# riffle-proto-0_1_8_0.net
KiCad netlist of a schematic drawn in EAGLE
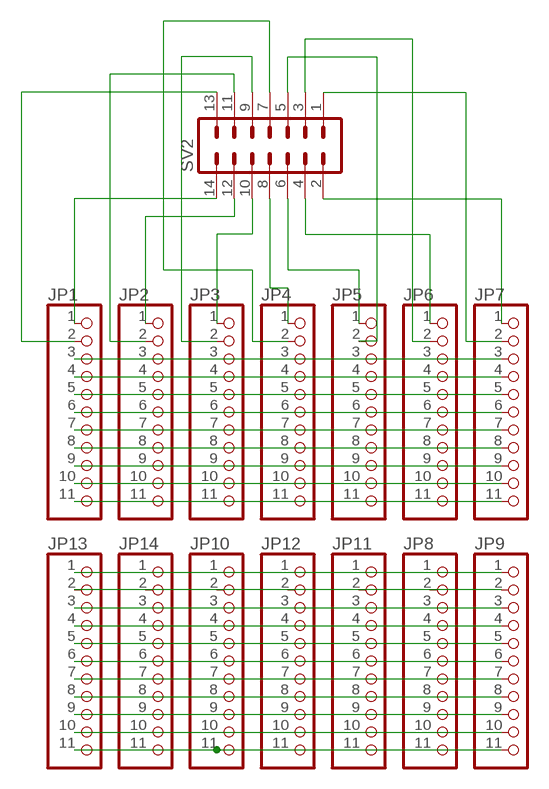
[diagram p0: schematic, sheet 1]

(export (version "E")
  (design (tool "Eeschema 10.0.6"))
  (components
    (comp (ref "JP1")
      (value "HEADER-1X1176MIL")
      (footprint "eagle-import:1X11_ROUND_76")
      (libsource (lib "eagle-import") (part "HEADER-1X1176MIL"))
    )
    (comp (ref "JP2")
      (value "HEADER-1X1176MIL")
      (footprint "eagle-import:1X11_ROUND_76")
      (libsource (lib "eagle-import") (part "HEADER-1X1176MIL"))
    )
    (comp (ref "JP3")
      (value "HEADER-1X1176MIL")
      (footprint "eagle-import:1X11_ROUND_76")
      (libsource (lib "eagle-import") (part "HEADER-1X1176MIL"))
    )
    (comp (ref "JP4")
      (value "HEADER-1X1176MIL")
      (footprint "eagle-import:1X11_ROUND_76")
      (libsource (lib "eagle-import") (part "HEADER-1X1176MIL"))
    )
    (comp (ref "JP5")
      (value "HEADER-1X1176MIL")
      (footprint "eagle-import:1X11_ROUND_76")
      (libsource (lib "eagle-import") (part "HEADER-1X1176MIL"))
    )
    (comp (ref "JP6")
      (value "HEADER-1X1176MIL")
      (footprint "eagle-import:1X11_ROUND_76")
      (libsource (lib "eagle-import") (part "HEADER-1X1176MIL"))
    )
    (comp (ref "JP7")
      (value "HEADER-1X1176MIL")
      (footprint "eagle-import:1X11_ROUND_76")
      (libsource (lib "eagle-import") (part "HEADER-1X1176MIL"))
    )
    (comp (ref "JP8")
      (value "HEADER-1X1176MIL")
      (footprint "eagle-import:1X11_ROUND_76")
      (libsource (lib "eagle-import") (part "HEADER-1X1176MIL"))
    )
    (comp (ref "JP9")
      (value "HEADER-1X1176MIL")
      (footprint "eagle-import:1X11_ROUND_76")
      (libsource (lib "eagle-import") (part "HEADER-1X1176MIL"))
    )
    (comp (ref "JP10")
      (value "HEADER-1X1176MIL")
      (footprint "eagle-import:1X11_ROUND_76")
      (libsource (lib "eagle-import") (part "HEADER-1X1176MIL"))
    )
    (comp (ref "JP11")
      (value "HEADER-1X1176MIL")
      (footprint "eagle-import:1X11_ROUND_76")
      (libsource (lib "eagle-import") (part "HEADER-1X1176MIL"))
    )
    (comp (ref "JP12")
      (value "HEADER-1X1176MIL")
      (footprint "eagle-import:1X11_ROUND_76")
      (libsource (lib "eagle-import") (part "HEADER-1X1176MIL"))
    )
    (comp (ref "JP13")
      (value "HEADER-1X1176MIL")
      (footprint "eagle-import:1X11_ROUND_76")
      (libsource (lib "eagle-import") (part "HEADER-1X1176MIL"))
    )
    (comp (ref "JP14")
      (value "HEADER-1X1176MIL")
      (footprint "eagle-import:1X11_ROUND_76")
      (libsource (lib "eagle-import") (part "HEADER-1X1176MIL"))
    )
    (comp (ref "SV2")
      (value "MA07-2")
      (footprint "eagle-import:MA07-2")
      (libsource (lib "eagle-import") (part "MA07-2"))
    )
  )
  (nets
    (net (code "1") (name "Net-(JP1-Pad1)") (class "Default")
      (node (ref "JP1") (pin "1") (pinfunction "1_1") (pintype "passive"))
      (node (ref "SV2") (pin "14") (pinfunction "14_14") (pintype "passive"))
    )
    (net (code "2") (name "Net-(JP1-Pad2)") (class "Default")
      (node (ref "JP1") (pin "2") (pinfunction "2_2") (pintype "passive"))
      (node (ref "SV2") (pin "13") (pinfunction "13_13") (pintype "passive"))
    )
    (net (code "3") (name "Net-(JP1-Pad3)") (class "Default")
      (node (ref "JP1") (pin "3") (pinfunction "3_3") (pintype "passive"))
      (node (ref "JP2") (pin "3") (pinfunction "3_3") (pintype "passive"))
      (node (ref "JP3") (pin "3") (pinfunction "3_3") (pintype "passive"))
      (node (ref "JP4") (pin "3") (pinfunction "3_3") (pintype "passive"))
      (node (ref "JP5") (pin "3") (pinfunction "3_3") (pintype "passive"))
      (node (ref "JP6") (pin "3") (pinfunction "3_3") (pintype "passive"))
      (node (ref "JP7") (pin "3") (pinfunction "3_3") (pintype "passive"))
    )
    (net (code "4") (name "Net-(JP1-Pad4)") (class "Default")
      (node (ref "JP1") (pin "4") (pinfunction "4_4") (pintype "passive"))
      (node (ref "JP2") (pin "4") (pinfunction "4_4") (pintype "passive"))
      (node (ref "JP3") (pin "4") (pinfunction "4_4") (pintype "passive"))
      (node (ref "JP4") (pin "4") (pinfunction "4_4") (pintype "passive"))
      (node (ref "JP5") (pin "4") (pinfunction "4_4") (pintype "passive"))
      (node (ref "JP6") (pin "4") (pinfunction "4_4") (pintype "passive"))
      (node (ref "JP7") (pin "4") (pinfunction "4_4") (pintype "passive"))
    )
    (net (code "5") (name "Net-(JP1-Pad5)") (class "Default")
      (node (ref "JP1") (pin "5") (pinfunction "5_5") (pintype "passive"))
      (node (ref "JP2") (pin "5") (pinfunction "5_5") (pintype "passive"))
      (node (ref "JP3") (pin "5") (pinfunction "5_5") (pintype "passive"))
      (node (ref "JP4") (pin "5") (pinfunction "5_5") (pintype "passive"))
      (node (ref "JP5") (pin "5") (pinfunction "5_5") (pintype "passive"))
      (node (ref "JP6") (pin "5") (pinfunction "5_5") (pintype "passive"))
      (node (ref "JP7") (pin "5") (pinfunction "5_5") (pintype "passive"))
    )
    (net (code "6") (name "Net-(JP1-Pad6)") (class "Default")
      (node (ref "JP1") (pin "6") (pinfunction "6_6") (pintype "passive"))
      (node (ref "JP2") (pin "6") (pinfunction "6_6") (pintype "passive"))
      (node (ref "JP3") (pin "6") (pinfunction "6_6") (pintype "passive"))
      (node (ref "JP4") (pin "6") (pinfunction "6_6") (pintype "passive"))
      (node (ref "JP5") (pin "6") (pinfunction "6_6") (pintype "passive"))
      (node (ref "JP6") (pin "6") (pinfunction "6_6") (pintype "passive"))
      (node (ref "JP7") (pin "6") (pinfunction "6_6") (pintype "passive"))
    )
    (net (code "7") (name "Net-(JP1-Pad7)") (class "Default")
      (node (ref "JP1") (pin "7") (pinfunction "7_7") (pintype "passive"))
      (node (ref "JP2") (pin "7") (pinfunction "7_7") (pintype "passive"))
      (node (ref "JP3") (pin "7") (pinfunction "7_7") (pintype "passive"))
      (node (ref "JP4") (pin "7") (pinfunction "7_7") (pintype "passive"))
      (node (ref "JP5") (pin "7") (pinfunction "7_7") (pintype "passive"))
      (node (ref "JP6") (pin "7") (pinfunction "7_7") (pintype "passive"))
      (node (ref "JP7") (pin "7") (pinfunction "7_7") (pintype "passive"))
    )
    (net (code "8") (name "Net-(JP1-Pad8)") (class "Default")
      (node (ref "JP1") (pin "8") (pinfunction "8_8") (pintype "passive"))
      (node (ref "JP2") (pin "8") (pinfunction "8_8") (pintype "passive"))
      (node (ref "JP3") (pin "8") (pinfunction "8_8") (pintype "passive"))
      (node (ref "JP4") (pin "8") (pinfunction "8_8") (pintype "passive"))
      (node (ref "JP5") (pin "8") (pinfunction "8_8") (pintype "passive"))
      (node (ref "JP6") (pin "8") (pinfunction "8_8") (pintype "passive"))
      (node (ref "JP7") (pin "8") (pinfunction "8_8") (pintype "passive"))
    )
    (net (code "9") (name "Net-(JP1-Pad9)") (class "Default")
      (node (ref "JP1") (pin "9") (pinfunction "9_9") (pintype "passive"))
      (node (ref "JP2") (pin "9") (pinfunction "9_9") (pintype "passive"))
      (node (ref "JP3") (pin "9") (pinfunction "9_9") (pintype "passive"))
      (node (ref "JP4") (pin "9") (pinfunction "9_9") (pintype "passive"))
      (node (ref "JP5") (pin "9") (pinfunction "9_9") (pintype "passive"))
      (node (ref "JP6") (pin "9") (pinfunction "9_9") (pintype "passive"))
      (node (ref "JP7") (pin "9") (pinfunction "9_9") (pintype "passive"))
    )
    (net (code "10") (name "Net-(JP1-Pad10)") (class "Default")
      (node (ref "JP1") (pin "10") (pinfunction "10_10") (pintype "passive"))
      (node (ref "JP2") (pin "10") (pinfunction "10_10") (pintype "passive"))
      (node (ref "JP3") (pin "10") (pinfunction "10_10") (pintype "passive"))
      (node (ref "JP4") (pin "10") (pinfunction "10_10") (pintype "passive"))
      (node (ref "JP5") (pin "10") (pinfunction "10_10") (pintype "passive"))
      (node (ref "JP6") (pin "10") (pinfunction "10_10") (pintype "passive"))
      (node (ref "JP7") (pin "10") (pinfunction "10_10") (pintype "passive"))
    )
    (net (code "11") (name "Net-(JP1-Pad11)") (class "Default")
      (node (ref "JP1") (pin "11") (pinfunction "11_11") (pintype "passive"))
      (node (ref "JP2") (pin "11") (pinfunction "11_11") (pintype "passive"))
      (node (ref "JP4") (pin "11") (pinfunction "11_11") (pintype "passive"))
      (node (ref "JP5") (pin "11") (pinfunction "11_11") (pintype "passive"))
      (node (ref "JP6") (pin "11") (pinfunction "11_11") (pintype "passive"))
      (node (ref "JP7") (pin "11") (pinfunction "11_11") (pintype "passive"))
    )
    (net (code "12") (name "Net-(JP2-Pad1)") (class "Default")
      (node (ref "JP2") (pin "1") (pinfunction "1_1") (pintype "passive"))
      (node (ref "SV2") (pin "12") (pinfunction "12_12") (pintype "passive"))
    )
    (net (code "13") (name "Net-(JP2-Pad2)") (class "Default")
      (node (ref "JP2") (pin "2") (pinfunction "2_2") (pintype "passive"))
      (node (ref "SV2") (pin "11") (pinfunction "11_11") (pintype "passive"))
    )
    (net (code "14") (name "Net-(JP3-Pad1)") (class "Default")
      (node (ref "JP3") (pin "1") (pinfunction "1_1") (pintype "passive"))
      (node (ref "SV2") (pin "10") (pinfunction "10_10") (pintype "passive"))
    )
    (net (code "15") (name "Net-(JP3-Pad2)") (class "Default")
      (node (ref "JP3") (pin "2") (pinfunction "2_2") (pintype "passive"))
      (node (ref "SV2") (pin "9") (pinfunction "9_9") (pintype "passive"))
    )
    (net (code "16") (name "Net-(JP4-Pad1)") (class "Default")
      (node (ref "JP4") (pin "1") (pinfunction "1_1") (pintype "passive"))
      (node (ref "SV2") (pin "8") (pinfunction "8_8") (pintype "passive"))
    )
    (net (code "17") (name "Net-(JP4-Pad2)") (class "Default")
      (node (ref "JP4") (pin "2") (pinfunction "2_2") (pintype "passive"))
      (node (ref "SV2") (pin "7") (pinfunction "7_7") (pintype "passive"))
    )
    (net (code "18") (name "Net-(JP5-Pad1)") (class "Default")
      (node (ref "JP5") (pin "1") (pinfunction "1_1") (pintype "passive"))
      (node (ref "SV2") (pin "6") (pinfunction "6_6") (pintype "passive"))
    )
    (net (code "19") (name "Net-(JP5-Pad2)") (class "Default")
      (node (ref "JP5") (pin "2") (pinfunction "2_2") (pintype "passive"))
      (node (ref "SV2") (pin "5") (pinfunction "5_5") (pintype "passive"))
    )
    (net (code "20") (name "Net-(JP6-Pad1)") (class "Default")
      (node (ref "JP6") (pin "1") (pinfunction "1_1") (pintype "passive"))
      (node (ref "SV2") (pin "4") (pinfunction "4_4") (pintype "passive"))
    )
    (net (code "21") (name "Net-(JP6-Pad2)") (class "Default")
      (node (ref "JP6") (pin "2") (pinfunction "2_2") (pintype "passive"))
      (node (ref "SV2") (pin "3") (pinfunction "3_3") (pintype "passive"))
    )
    (net (code "22") (name "Net-(JP7-Pad1)") (class "Default")
      (node (ref "JP7") (pin "1") (pinfunction "1_1") (pintype "passive"))
      (node (ref "SV2") (pin "2") (pinfunction "2_2") (pintype "passive"))
    )
    (net (code "23") (name "Net-(JP7-Pad2)") (class "Default")
      (node (ref "JP7") (pin "2") (pinfunction "2_2") (pintype "passive"))
      (node (ref "SV2") (pin "1") (pinfunction "1_1") (pintype "passive"))
    )
    (net (code "24") (name "Net-(JP10-Pad1)") (class "Default")
      (node (ref "JP10") (pin "1") (pinfunction "1_1") (pintype "passive"))
      (node (ref "JP11") (pin "1") (pinfunction "1_1") (pintype "passive"))
      (node (ref "JP12") (pin "1") (pinfunction "1_1") (pintype "passive"))
      (node (ref "JP13") (pin "1") (pinfunction "1_1") (pintype "passive"))
      (node (ref "JP14") (pin "1") (pinfunction "1_1") (pintype "passive"))
      (node (ref "JP8") (pin "1") (pinfunction "1_1") (pintype "passive"))
      (node (ref "JP9") (pin "1") (pinfunction "1_1") (pintype "passive"))
    )
    (net (code "25") (name "Net-(JP10-Pad2)") (class "Default")
      (node (ref "JP10") (pin "2") (pinfunction "2_2") (pintype "passive"))
      (node (ref "JP11") (pin "2") (pinfunction "2_2") (pintype "passive"))
      (node (ref "JP12") (pin "2") (pinfunction "2_2") (pintype "passive"))
      (node (ref "JP13") (pin "2") (pinfunction "2_2") (pintype "passive"))
      (node (ref "JP14") (pin "2") (pinfunction "2_2") (pintype "passive"))
      (node (ref "JP8") (pin "2") (pinfunction "2_2") (pintype "passive"))
      (node (ref "JP9") (pin "2") (pinfunction "2_2") (pintype "passive"))
    )
    (net (code "26") (name "Net-(JP10-Pad3)") (class "Default")
      (node (ref "JP10") (pin "3") (pinfunction "3_3") (pintype "passive"))
      (node (ref "JP11") (pin "3") (pinfunction "3_3") (pintype "passive"))
      (node (ref "JP12") (pin "3") (pinfunction "3_3") (pintype "passive"))
      (node (ref "JP13") (pin "3") (pinfunction "3_3") (pintype "passive"))
      (node (ref "JP14") (pin "3") (pinfunction "3_3") (pintype "passive"))
      (node (ref "JP8") (pin "3") (pinfunction "3_3") (pintype "passive"))
      (node (ref "JP9") (pin "3") (pinfunction "3_3") (pintype "passive"))
    )
    (net (code "27") (name "Net-(JP10-Pad4)") (class "Default")
      (node (ref "JP10") (pin "4") (pinfunction "4_4") (pintype "passive"))
      (node (ref "JP11") (pin "4") (pinfunction "4_4") (pintype "passive"))
      (node (ref "JP12") (pin "4") (pinfunction "4_4") (pintype "passive"))
      (node (ref "JP13") (pin "4") (pinfunction "4_4") (pintype "passive"))
      (node (ref "JP14") (pin "4") (pinfunction "4_4") (pintype "passive"))
      (node (ref "JP8") (pin "4") (pinfunction "4_4") (pintype "passive"))
      (node (ref "JP9") (pin "4") (pinfunction "4_4") (pintype "passive"))
    )
    (net (code "28") (name "Net-(JP10-Pad5)") (class "Default")
      (node (ref "JP10") (pin "5") (pinfunction "5_5") (pintype "passive"))
      (node (ref "JP11") (pin "5") (pinfunction "5_5") (pintype "passive"))
      (node (ref "JP12") (pin "5") (pinfunction "5_5") (pintype "passive"))
      (node (ref "JP13") (pin "5") (pinfunction "5_5") (pintype "passive"))
      (node (ref "JP14") (pin "5") (pinfunction "5_5") (pintype "passive"))
      (node (ref "JP8") (pin "5") (pinfunction "5_5") (pintype "passive"))
      (node (ref "JP9") (pin "5") (pinfunction "5_5") (pintype "passive"))
    )
    (net (code "29") (name "Net-(JP10-Pad6)") (class "Default")
      (node (ref "JP10") (pin "6") (pinfunction "6_6") (pintype "passive"))
      (node (ref "JP11") (pin "6") (pinfunction "6_6") (pintype "passive"))
      (node (ref "JP12") (pin "6") (pinfunction "6_6") (pintype "passive"))
      (node (ref "JP13") (pin "6") (pinfunction "6_6") (pintype "passive"))
      (node (ref "JP14") (pin "6") (pinfunction "6_6") (pintype "passive"))
      (node (ref "JP8") (pin "6") (pinfunction "6_6") (pintype "passive"))
      (node (ref "JP9") (pin "6") (pinfunction "6_6") (pintype "passive"))
    )
    (net (code "30") (name "Net-(JP10-Pad7)") (class "Default")
      (node (ref "JP10") (pin "7") (pinfunction "7_7") (pintype "passive"))
      (node (ref "JP11") (pin "7") (pinfunction "7_7") (pintype "passive"))
      (node (ref "JP12") (pin "7") (pinfunction "7_7") (pintype "passive"))
      (node (ref "JP13") (pin "7") (pinfunction "7_7") (pintype "passive"))
      (node (ref "JP14") (pin "7") (pinfunction "7_7") (pintype "passive"))
      (node (ref "JP8") (pin "7") (pinfunction "7_7") (pintype "passive"))
      (node (ref "JP9") (pin "7") (pinfunction "7_7") (pintype "passive"))
    )
    (net (code "31") (name "Net-(JP10-Pad8)") (class "Default")
      (node (ref "JP10") (pin "8") (pinfunction "8_8") (pintype "passive"))
      (node (ref "JP11") (pin "8") (pinfunction "8_8") (pintype "passive"))
      (node (ref "JP12") (pin "8") (pinfunction "8_8") (pintype "passive"))
      (node (ref "JP13") (pin "8") (pinfunction "8_8") (pintype "passive"))
      (node (ref "JP14") (pin "8") (pinfunction "8_8") (pintype "passive"))
      (node (ref "JP8") (pin "8") (pinfunction "8_8") (pintype "passive"))
      (node (ref "JP9") (pin "8") (pinfunction "8_8") (pintype "passive"))
    )
    (net (code "32") (name "Net-(JP10-Pad9)") (class "Default")
      (node (ref "JP10") (pin "9") (pinfunction "9_9") (pintype "passive"))
      (node (ref "JP11") (pin "9") (pinfunction "9_9") (pintype "passive"))
      (node (ref "JP12") (pin "9") (pinfunction "9_9") (pintype "passive"))
      (node (ref "JP13") (pin "9") (pinfunction "9_9") (pintype "passive"))
      (node (ref "JP14") (pin "9") (pinfunction "9_9") (pintype "passive"))
      (node (ref "JP8") (pin "9") (pinfunction "9_9") (pintype "passive"))
      (node (ref "JP9") (pin "9") (pinfunction "9_9") (pintype "passive"))
    )
    (net (code "33") (name "Net-(JP10-Pad10)") (class "Default")
      (node (ref "JP10") (pin "10") (pinfunction "10_10") (pintype "passive"))
      (node (ref "JP11") (pin "10") (pinfunction "10_10") (pintype "passive"))
      (node (ref "JP12") (pin "10") (pinfunction "10_10") (pintype "passive"))
      (node (ref "JP13") (pin "10") (pinfunction "10_10") (pintype "passive"))
      (node (ref "JP14") (pin "10") (pinfunction "10_10") (pintype "passive"))
      (node (ref "JP8") (pin "10") (pinfunction "10_10") (pintype "passive"))
      (node (ref "JP9") (pin "10") (pinfunction "10_10") (pintype "passive"))
    )
    (net (code "34") (name "Net-(JP10-Pad11)") (class "Default")
      (node (ref "JP10") (pin "11") (pinfunction "11_11") (pintype "passive"))
      (node (ref "JP11") (pin "11") (pinfunction "11_11") (pintype "passive"))
      (node (ref "JP12") (pin "11") (pinfunction "11_11") (pintype "passive"))
      (node (ref "JP13") (pin "11") (pinfunction "11_11") (pintype "passive"))
      (node (ref "JP14") (pin "11") (pinfunction "11_11") (pintype "passive"))
      (node (ref "JP8") (pin "11") (pinfunction "11_11") (pintype "passive"))
      (node (ref "JP9") (pin "11") (pinfunction "11_11") (pintype "passive"))
    )
    (net (code "35") (name "unconnected-(JP3-Pad11)") (class "Default")
      (node (ref "JP3") (pin "11") (pinfunction "11_11") (pintype "passive"))
    )
  )
)
